# booz_imu_yz.net
KiCad netlist of a schematic drawn in EAGLE
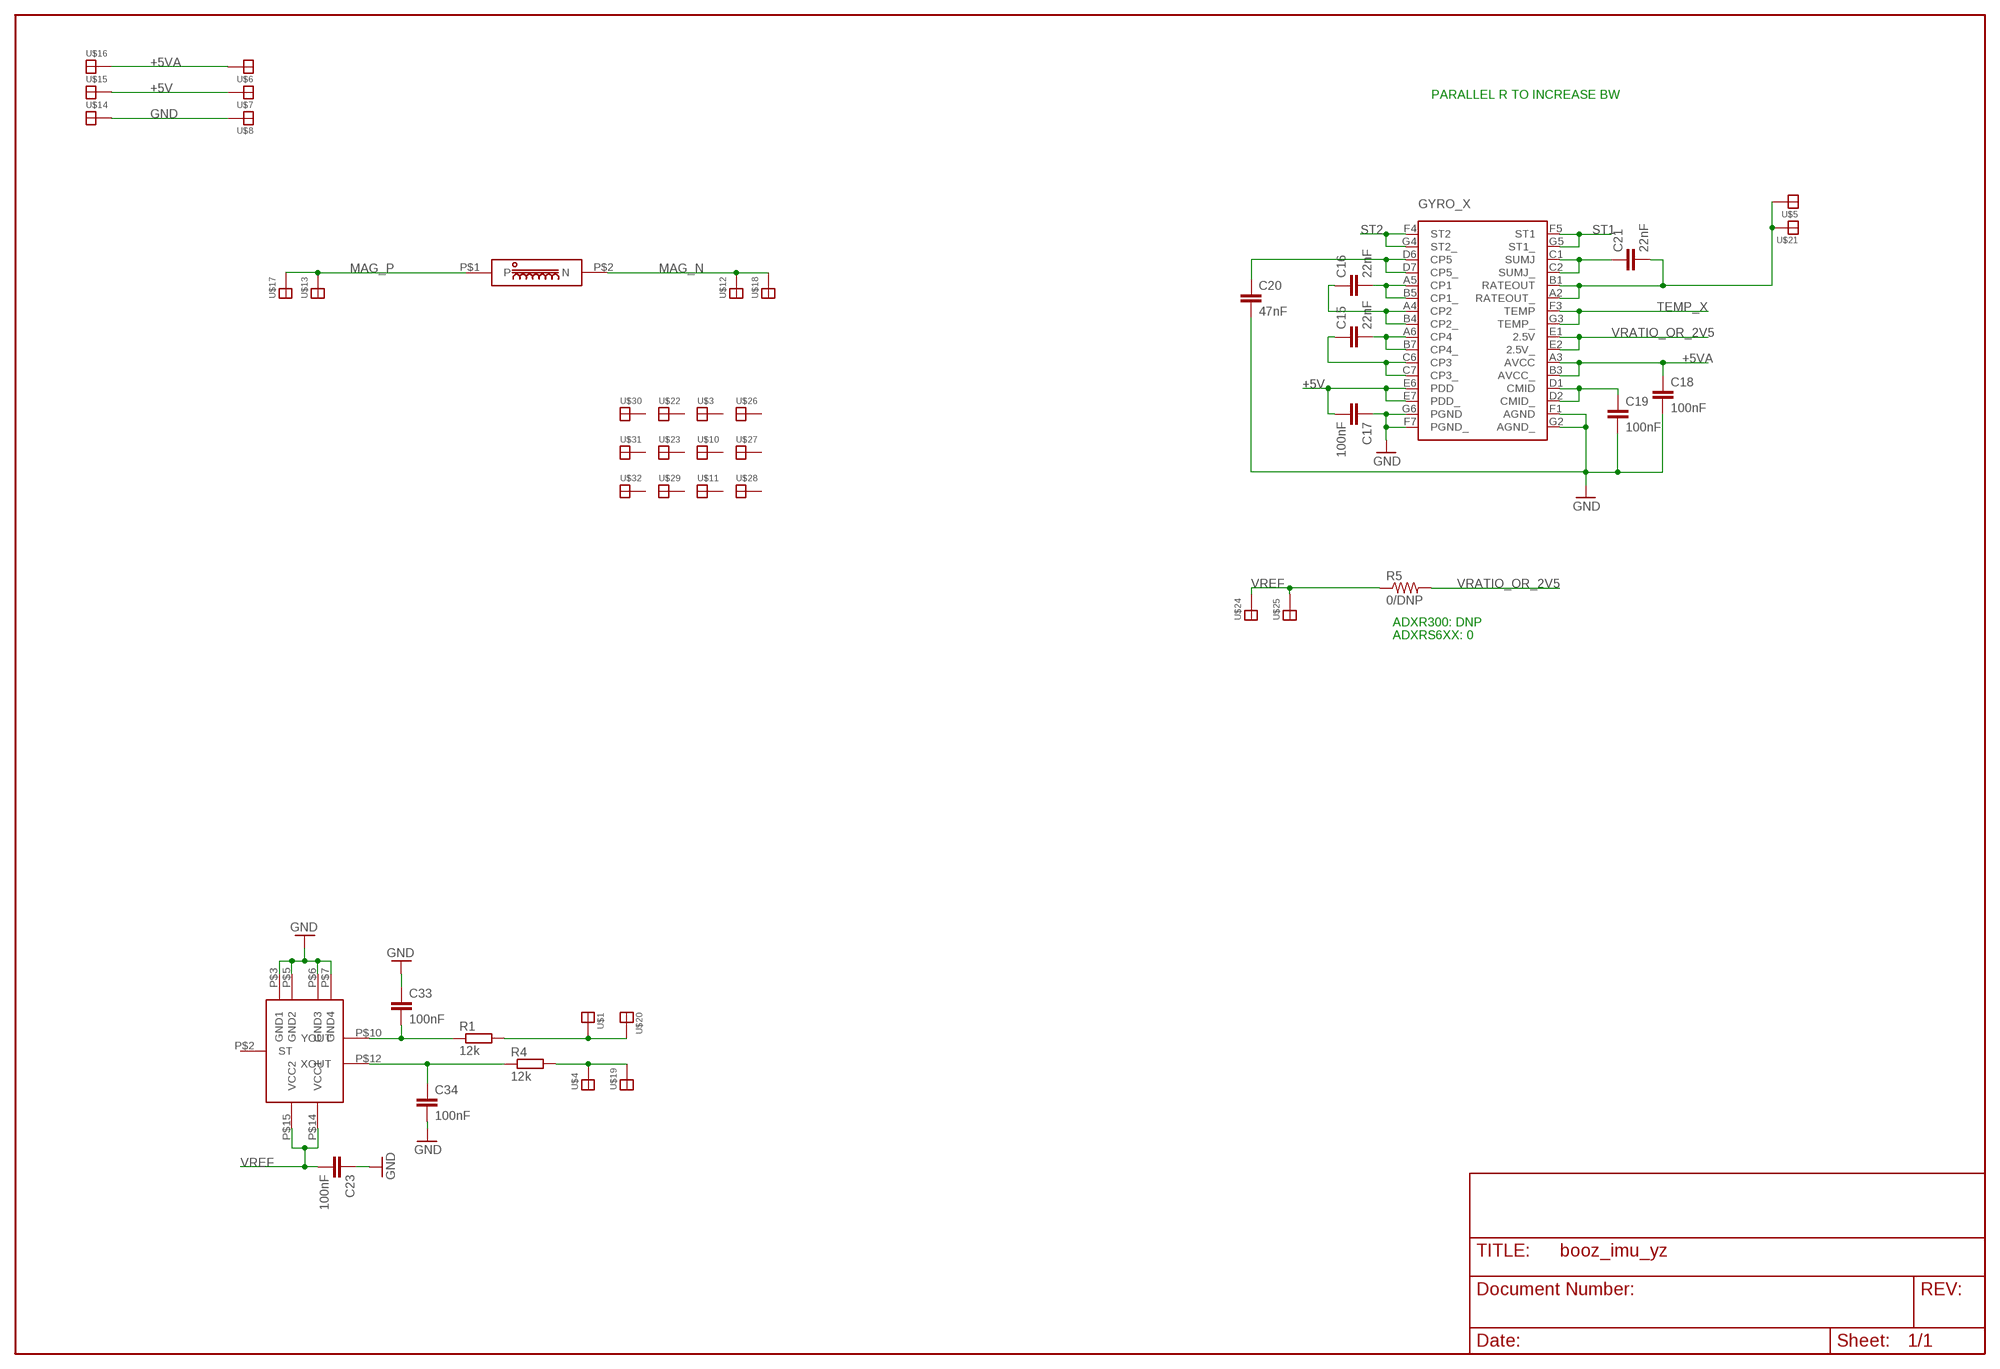
[diagram p0: schematic, sheet 1]

(export (version "E")
  (design (tool "Eeschema 10.0.6"))
  (components
    (comp (ref "C15")
      (value "22nF")
      (footprint "eagle-import:C0603K")
      (libsource (lib "eagle-import") (part "C-EUC0603K"))
    )
    (comp (ref "C16")
      (value "22nF")
      (footprint "eagle-import:C0603K")
      (libsource (lib "eagle-import") (part "C-EUC0603K"))
    )
    (comp (ref "C17")
      (value "100nF")
      (footprint "eagle-import:C0603K")
      (libsource (lib "eagle-import") (part "C-EUC0603K"))
    )
    (comp (ref "C18")
      (value "100nF")
      (footprint "eagle-import:C0603K")
      (libsource (lib "eagle-import") (part "C-EUC0603K"))
    )
    (comp (ref "C19")
      (value "100nF")
      (footprint "eagle-import:C0603K")
      (libsource (lib "eagle-import") (part "C-EUC0603K"))
    )
    (comp (ref "C20")
      (value "47nF")
      (footprint "eagle-import:C0603K")
      (libsource (lib "eagle-import") (part "C-EUC0603K"))
    )
    (comp (ref "C21")
      (value "22nF")
      (footprint "eagle-import:C0603K")
      (libsource (lib "eagle-import") (part "C-EUC0603K"))
    )
    (comp (ref "C23")
      (value "100nF")
      (footprint "eagle-import:C0603K")
      (libsource (lib "eagle-import") (part "C-EUC0603K"))
    )
    (comp (ref "C33")
      (value "100nF")
      (footprint "eagle-import:C0603K")
      (libsource (lib "eagle-import") (part "C-EUC0603K"))
    )
    (comp (ref "C34")
      (value "100nF")
      (footprint "eagle-import:C0603K")
      (libsource (lib "eagle-import") (part "C-EUC0603K"))
    )
    (comp (ref "GYRO_X")
      (value "ADXR")
      (footprint "eagle-import:BC-32")
      (libsource (lib "eagle-import") (part "ADXR"))
    )
    (comp (ref "R1")
      (value "12k")
      (footprint "eagle-import:R0603")
      (libsource (lib "eagle-import") (part "R-EU_R0603"))
    )
    (comp (ref "R4")
      (value "12k")
      (footprint "eagle-import:R0603")
      (libsource (lib "eagle-import") (part "R-EU_R0603"))
    )
    (comp (ref "R5")
      (value "0/DNP")
      (footprint "eagle-import:R0603")
      (libsource (lib "eagle-import") (part "R-US_R0603"))
    )
    (comp (ref "U$1")
      (value "SOLDER_PAD")
      (footprint "eagle-import:SOLDER_PAD")
      (libsource (lib "eagle-import") (part "SOLDER_PAD"))
    )
    (comp (ref "U$2")
      (value "ADXL320")
      (footprint "eagle-import:LSCFP")
      (libsource (lib "eagle-import") (part "ADXL320"))
    )
    (comp (ref "U$3")
      (value "SOLDER_PAD")
      (footprint "eagle-import:SOLDER_PAD")
      (libsource (lib "eagle-import") (part "SOLDER_PAD"))
    )
    (comp (ref "U$4")
      (value "SOLDER_PAD")
      (footprint "eagle-import:SOLDER_PAD")
      (libsource (lib "eagle-import") (part "SOLDER_PAD"))
    )
    (comp (ref "U$5")
      (value "SOLDER_PAD")
      (footprint "eagle-import:SOLDER_PAD")
      (libsource (lib "eagle-import") (part "SOLDER_PAD"))
    )
    (comp (ref "U$6")
      (value "SOLDER_PAD")
      (footprint "eagle-import:SOLDER_PAD")
      (libsource (lib "eagle-import") (part "SOLDER_PAD"))
    )
    (comp (ref "U$7")
      (value "SOLDER_PAD")
      (footprint "eagle-import:SOLDER_PAD")
      (libsource (lib "eagle-import") (part "SOLDER_PAD"))
    )
    (comp (ref "U$8")
      (value "SOLDER_PAD")
      (footprint "eagle-import:SOLDER_PAD")
      (libsource (lib "eagle-import") (part "SOLDER_PAD"))
    )
    (comp (ref "U$9")
      (value "SEN_XY")
      (footprint "eagle-import:SEN_XY")
      (libsource (lib "eagle-import") (part "SEN_XY"))
    )
    (comp (ref "U$10")
      (value "SOLDER_PAD")
      (footprint "eagle-import:SOLDER_PAD")
      (libsource (lib "eagle-import") (part "SOLDER_PAD"))
    )
    (comp (ref "U$11")
      (value "SOLDER_PAD")
      (footprint "eagle-import:SOLDER_PAD")
      (libsource (lib "eagle-import") (part "SOLDER_PAD"))
    )
    (comp (ref "U$12")
      (value "SOLDER_PAD")
      (footprint "eagle-import:SOLDER_PAD")
      (libsource (lib "eagle-import") (part "SOLDER_PAD"))
    )
    (comp (ref "U$13")
      (value "SOLDER_PAD")
      (footprint "eagle-import:SOLDER_PAD")
      (libsource (lib "eagle-import") (part "SOLDER_PAD"))
    )
    (comp (ref "U$14")
      (value "SOLDER_PAD")
      (footprint "eagle-import:SOLDER_PAD")
      (libsource (lib "eagle-import") (part "SOLDER_PAD"))
    )
    (comp (ref "U$15")
      (value "SOLDER_PAD")
      (footprint "eagle-import:SOLDER_PAD")
      (libsource (lib "eagle-import") (part "SOLDER_PAD"))
    )
    (comp (ref "U$16")
      (value "SOLDER_PAD")
      (footprint "eagle-import:SOLDER_PAD")
      (libsource (lib "eagle-import") (part "SOLDER_PAD"))
    )
    (comp (ref "U$17")
      (value "SOLDER_PAD")
      (footprint "eagle-import:SOLDER_PAD")
      (libsource (lib "eagle-import") (part "SOLDER_PAD"))
    )
    (comp (ref "U$18")
      (value "SOLDER_PAD")
      (footprint "eagle-import:SOLDER_PAD")
      (libsource (lib "eagle-import") (part "SOLDER_PAD"))
    )
    (comp (ref "U$19")
      (value "SOLDER_PAD")
      (footprint "eagle-import:SOLDER_PAD")
      (libsource (lib "eagle-import") (part "SOLDER_PAD"))
    )
    (comp (ref "U$20")
      (value "SOLDER_PAD")
      (footprint "eagle-import:SOLDER_PAD")
      (libsource (lib "eagle-import") (part "SOLDER_PAD"))
    )
    (comp (ref "U$21")
      (value "SOLDER_PAD")
      (footprint "eagle-import:SOLDER_PAD")
      (libsource (lib "eagle-import") (part "SOLDER_PAD"))
    )
    (comp (ref "U$22")
      (value "SOLDER_PAD")
      (footprint "eagle-import:SOLDER_PAD")
      (libsource (lib "eagle-import") (part "SOLDER_PAD"))
    )
    (comp (ref "U$23")
      (value "SOLDER_PAD")
      (footprint "eagle-import:SOLDER_PAD")
      (libsource (lib "eagle-import") (part "SOLDER_PAD"))
    )
    (comp (ref "U$24")
      (value "SOLDER_PAD")
      (footprint "eagle-import:SOLDER_PAD")
      (libsource (lib "eagle-import") (part "SOLDER_PAD"))
    )
    (comp (ref "U$25")
      (value "SOLDER_PAD")
      (footprint "eagle-import:SOLDER_PAD")
      (libsource (lib "eagle-import") (part "SOLDER_PAD"))
    )
    (comp (ref "U$26")
      (value "SOLDER_PAD")
      (footprint "eagle-import:SOLDER_PAD")
      (libsource (lib "eagle-import") (part "SOLDER_PAD"))
    )
    (comp (ref "U$27")
      (value "SOLDER_PAD")
      (footprint "eagle-import:SOLDER_PAD")
      (libsource (lib "eagle-import") (part "SOLDER_PAD"))
    )
    (comp (ref "U$28")
      (value "SOLDER_PAD")
      (footprint "eagle-import:SOLDER_PAD")
      (libsource (lib "eagle-import") (part "SOLDER_PAD"))
    )
    (comp (ref "U$29")
      (value "SOLDER_PAD")
      (footprint "eagle-import:SOLDER_PAD")
      (libsource (lib "eagle-import") (part "SOLDER_PAD"))
    )
    (comp (ref "U$30")
      (value "SOLDER_PAD")
      (footprint "eagle-import:SOLDER_PAD")
      (libsource (lib "eagle-import") (part "SOLDER_PAD"))
    )
    (comp (ref "U$31")
      (value "SOLDER_PAD")
      (footprint "eagle-import:SOLDER_PAD")
      (libsource (lib "eagle-import") (part "SOLDER_PAD"))
    )
    (comp (ref "U$32")
      (value "SOLDER_PAD")
      (footprint "eagle-import:SOLDER_PAD")
      (libsource (lib "eagle-import") (part "SOLDER_PAD"))
    )
  )
  (nets
    (net (code "1") (name "/+5V") (class "Default")
      (node (ref "C17") (pin "2") (pinfunction "2_2") (pintype "passive"))
      (node (ref "GYRO_X") (pin "E6") (pinfunction "PDD_E6") (pintype "bidirectional"))
      (node (ref "GYRO_X") (pin "E7") (pinfunction "PDD__E7") (pintype "bidirectional"))
      (node (ref "U$15") (pin "P$1") (pinfunction "P$1_P$1") (pintype "bidirectional"))
      (node (ref "U$7") (pin "P$1") (pinfunction "P$1_P$1") (pintype "bidirectional"))
    )
    (net (code "2") (name "/+5VA") (class "Default")
      (node (ref "C18") (pin "1") (pinfunction "1_1") (pintype "passive"))
      (node (ref "GYRO_X") (pin "A3") (pinfunction "AVCC_A3") (pintype "bidirectional"))
      (node (ref "GYRO_X") (pin "B3") (pinfunction "AVCC__B3") (pintype "bidirectional"))
      (node (ref "U$16") (pin "P$1") (pinfunction "P$1_P$1") (pintype "bidirectional"))
      (node (ref "U$6") (pin "P$1") (pinfunction "P$1_P$1") (pintype "bidirectional"))
    )
    (net (code "3") (name "/MAG_N") (class "Default")
      (node (ref "U$12") (pin "P$1") (pinfunction "P$1_P$1") (pintype "bidirectional"))
      (node (ref "U$18") (pin "P$1") (pinfunction "P$1_P$1") (pintype "bidirectional"))
      (node (ref "U$9") (pin "P$2") (pinfunction "N_P$2") (pintype "bidirectional"))
    )
    (net (code "4") (name "/MAG_P") (class "Default")
      (node (ref "U$13") (pin "P$1") (pinfunction "P$1_P$1") (pintype "bidirectional"))
      (node (ref "U$17") (pin "P$1") (pinfunction "P$1_P$1") (pintype "bidirectional"))
      (node (ref "U$9") (pin "P$1") (pinfunction "P_P$1") (pintype "bidirectional"))
    )
    (net (code "5") (name "/ST1") (class "Default")
      (node (ref "GYRO_X") (pin "F5") (pinfunction "ST1_F5") (pintype "bidirectional"))
      (node (ref "GYRO_X") (pin "G5") (pinfunction "ST1__G5") (pintype "bidirectional"))
    )
    (net (code "6") (name "/ST2") (class "Default")
      (node (ref "GYRO_X") (pin "F4") (pinfunction "ST2_F4") (pintype "bidirectional"))
      (node (ref "GYRO_X") (pin "G4") (pinfunction "ST2__G4") (pintype "bidirectional"))
    )
    (net (code "7") (name "/TEMP_X") (class "Default")
      (node (ref "GYRO_X") (pin "F3") (pinfunction "TEMP_F3") (pintype "bidirectional"))
      (node (ref "GYRO_X") (pin "G3") (pinfunction "TEMP__G3") (pintype "bidirectional"))
    )
    (net (code "8") (name "/VRATIO_OR_2V5") (class "Default")
      (node (ref "GYRO_X") (pin "E1") (pinfunction "2.5V_E1") (pintype "bidirectional"))
      (node (ref "GYRO_X") (pin "E2") (pinfunction "2.5V__E2") (pintype "bidirectional"))
      (node (ref "R5") (pin "2") (pinfunction "2_2") (pintype "passive"))
    )
    (net (code "9") (name "/VREF") (class "Default")
      (node (ref "C23") (pin "2") (pinfunction "2_2") (pintype "passive"))
      (node (ref "R5") (pin "1") (pinfunction "1_1") (pintype "passive"))
      (node (ref "U$2") (pin "P$14") (pinfunction "VCC1_P$14") (pintype "bidirectional"))
      (node (ref "U$2") (pin "P$15") (pinfunction "VCC2_P$15") (pintype "bidirectional"))
      (node (ref "U$24") (pin "P$1") (pinfunction "P$1_P$1") (pintype "bidirectional"))
      (node (ref "U$25") (pin "P$1") (pinfunction "P$1_P$1") (pintype "bidirectional"))
    )
    (net (code "10") (name "GND") (class "Default")
      (node (ref "C17") (pin "1") (pinfunction "1_1") (pintype "passive"))
      (node (ref "C18") (pin "2") (pinfunction "2_2") (pintype "passive"))
      (node (ref "C19") (pin "2") (pinfunction "2_2") (pintype "passive"))
      (node (ref "C20") (pin "2") (pinfunction "2_2") (pintype "passive"))
      (node (ref "C23") (pin "1") (pinfunction "1_1") (pintype "passive"))
      (node (ref "C33") (pin "1") (pinfunction "1_1") (pintype "passive"))
      (node (ref "C34") (pin "2") (pinfunction "2_2") (pintype "passive"))
      (node (ref "GYRO_X") (pin "F1") (pinfunction "AGND_F1") (pintype "bidirectional"))
      (node (ref "GYRO_X") (pin "F7") (pinfunction "PGND__F7") (pintype "bidirectional"))
      (node (ref "GYRO_X") (pin "G2") (pinfunction "AGND__G2") (pintype "bidirectional"))
      (node (ref "GYRO_X") (pin "G6") (pinfunction "PGND_G6") (pintype "bidirectional"))
      (node (ref "U$14") (pin "P$1") (pinfunction "P$1_P$1") (pintype "bidirectional"))
      (node (ref "U$2") (pin "P$3") (pinfunction "GND1_P$3") (pintype "bidirectional"))
      (node (ref "U$2") (pin "P$5") (pinfunction "GND2_P$5") (pintype "bidirectional"))
      (node (ref "U$2") (pin "P$6") (pinfunction "GND3_P$6") (pintype "bidirectional"))
      (node (ref "U$2") (pin "P$7") (pinfunction "GND4_P$7") (pintype "bidirectional"))
      (node (ref "U$8") (pin "P$1") (pinfunction "P$1_P$1") (pintype "bidirectional"))
    )
    (net (code "11") (name "Net-(GYRO_X-CMID)") (class "Default")
      (node (ref "C19") (pin "1") (pinfunction "1_1") (pintype "passive"))
      (node (ref "GYRO_X") (pin "D1") (pinfunction "CMID_D1") (pintype "bidirectional"))
      (node (ref "GYRO_X") (pin "D2") (pinfunction "CMID__D2") (pintype "bidirectional"))
    )
    (net (code "12") (name "Net-(GYRO_X-CP1)") (class "Default")
      (node (ref "C16") (pin "2") (pinfunction "2_2") (pintype "passive"))
      (node (ref "GYRO_X") (pin "A5") (pinfunction "CP1_A5") (pintype "bidirectional"))
      (node (ref "GYRO_X") (pin "B5") (pinfunction "CP1__B5") (pintype "bidirectional"))
    )
    (net (code "13") (name "Net-(GYRO_X-CP2)") (class "Default")
      (node (ref "C16") (pin "1") (pinfunction "1_1") (pintype "passive"))
      (node (ref "GYRO_X") (pin "A4") (pinfunction "CP2_A4") (pintype "bidirectional"))
      (node (ref "GYRO_X") (pin "B4") (pinfunction "CP2__B4") (pintype "bidirectional"))
    )
    (net (code "14") (name "Net-(GYRO_X-CP3)") (class "Default")
      (node (ref "C15") (pin "1") (pinfunction "1_1") (pintype "passive"))
      (node (ref "GYRO_X") (pin "C6") (pinfunction "CP3_C6") (pintype "bidirectional"))
      (node (ref "GYRO_X") (pin "C7") (pinfunction "CP3__C7") (pintype "bidirectional"))
    )
    (net (code "15") (name "Net-(GYRO_X-CP4)") (class "Default")
      (node (ref "C15") (pin "2") (pinfunction "2_2") (pintype "passive"))
      (node (ref "GYRO_X") (pin "A6") (pinfunction "CP4_A6") (pintype "bidirectional"))
      (node (ref "GYRO_X") (pin "B7") (pinfunction "CP4__B7") (pintype "bidirectional"))
    )
    (net (code "16") (name "Net-(GYRO_X-CP5)") (class "Default")
      (node (ref "C20") (pin "1") (pinfunction "1_1") (pintype "passive"))
      (node (ref "GYRO_X") (pin "D6") (pinfunction "CP5_D6") (pintype "bidirectional"))
      (node (ref "GYRO_X") (pin "D7") (pinfunction "CP5__D7") (pintype "bidirectional"))
    )
    (net (code "17") (name "Net-(GYRO_X-RATEOUT)") (class "Default")
      (node (ref "C21") (pin "2") (pinfunction "2_2") (pintype "passive"))
      (node (ref "GYRO_X") (pin "A2") (pinfunction "RATEOUT__A2") (pintype "bidirectional"))
      (node (ref "GYRO_X") (pin "B1") (pinfunction "RATEOUT_B1") (pintype "bidirectional"))
      (node (ref "U$21") (pin "P$1") (pinfunction "P$1_P$1") (pintype "bidirectional"))
      (node (ref "U$5") (pin "P$1") (pinfunction "P$1_P$1") (pintype "bidirectional"))
    )
    (net (code "18") (name "Net-(GYRO_X-SUMJ)") (class "Default")
      (node (ref "C21") (pin "1") (pinfunction "1_1") (pintype "passive"))
      (node (ref "GYRO_X") (pin "C1") (pinfunction "SUMJ_C1") (pintype "bidirectional"))
      (node (ref "GYRO_X") (pin "C2") (pinfunction "SUMJ__C2") (pintype "bidirectional"))
    )
    (net (code "19") (name "Net-(R1-Pad2)") (class "Default")
      (node (ref "R1") (pin "2") (pinfunction "2_2") (pintype "passive"))
      (node (ref "U$1") (pin "P$1") (pinfunction "P$1_P$1") (pintype "bidirectional"))
      (node (ref "U$20") (pin "P$1") (pinfunction "P$1_P$1") (pintype "bidirectional"))
    )
    (net (code "20") (name "Net-(R4-Pad2)") (class "Default")
      (node (ref "R4") (pin "2") (pinfunction "2_2") (pintype "passive"))
      (node (ref "U$19") (pin "P$1") (pinfunction "P$1_P$1") (pintype "bidirectional"))
      (node (ref "U$4") (pin "P$1") (pinfunction "P$1_P$1") (pintype "bidirectional"))
    )
    (net (code "21") (name "Net-(U$2-XOUT)") (class "Default")
      (node (ref "C34") (pin "1") (pinfunction "1_1") (pintype "passive"))
      (node (ref "R4") (pin "1") (pinfunction "1_1") (pintype "passive"))
      (node (ref "U$2") (pin "P$12") (pinfunction "XOUT_P$12") (pintype "bidirectional"))
    )
    (net (code "22") (name "Net-(U$2-YOUT)") (class "Default")
      (node (ref "C33") (pin "2") (pinfunction "2_2") (pintype "passive"))
      (node (ref "R1") (pin "1") (pinfunction "1_1") (pintype "passive"))
      (node (ref "U$2") (pin "P$10") (pinfunction "YOUT_P$10") (pintype "bidirectional"))
    )
    (net (code "23") (name "unconnected-(U$2-ST-PadP$2)") (class "Default")
      (node (ref "U$2") (pin "P$2") (pinfunction "ST_P$2") (pintype "bidirectional"))
    )
    (net (code "24") (name "unconnected-(U$3-PadP$1)") (class "Default")
      (node (ref "U$3") (pin "P$1") (pinfunction "P$1_P$1") (pintype "bidirectional"))
    )
    (net (code "25") (name "unconnected-(U$10-PadP$1)") (class "Default")
      (node (ref "U$10") (pin "P$1") (pinfunction "P$1_P$1") (pintype "bidirectional"))
    )
    (net (code "26") (name "unconnected-(U$11-PadP$1)") (class "Default")
      (node (ref "U$11") (pin "P$1") (pinfunction "P$1_P$1") (pintype "bidirectional"))
    )
    (net (code "27") (name "unconnected-(U$22-PadP$1)") (class "Default")
      (node (ref "U$22") (pin "P$1") (pinfunction "P$1_P$1") (pintype "bidirectional"))
    )
    (net (code "28") (name "unconnected-(U$23-PadP$1)") (class "Default")
      (node (ref "U$23") (pin "P$1") (pinfunction "P$1_P$1") (pintype "bidirectional"))
    )
    (net (code "29") (name "unconnected-(U$26-PadP$1)") (class "Default")
      (node (ref "U$26") (pin "P$1") (pinfunction "P$1_P$1") (pintype "bidirectional"))
    )
    (net (code "30") (name "unconnected-(U$27-PadP$1)") (class "Default")
      (node (ref "U$27") (pin "P$1") (pinfunction "P$1_P$1") (pintype "bidirectional"))
    )
    (net (code "31") (name "unconnected-(U$28-PadP$1)") (class "Default")
      (node (ref "U$28") (pin "P$1") (pinfunction "P$1_P$1") (pintype "bidirectional"))
    )
    (net (code "32") (name "unconnected-(U$29-PadP$1)") (class "Default")
      (node (ref "U$29") (pin "P$1") (pinfunction "P$1_P$1") (pintype "bidirectional"))
    )
    (net (code "33") (name "unconnected-(U$30-PadP$1)") (class "Default")
      (node (ref "U$30") (pin "P$1") (pinfunction "P$1_P$1") (pintype "bidirectional"))
    )
    (net (code "34") (name "unconnected-(U$31-PadP$1)") (class "Default")
      (node (ref "U$31") (pin "P$1") (pinfunction "P$1_P$1") (pintype "bidirectional"))
    )
    (net (code "35") (name "unconnected-(U$32-PadP$1)") (class "Default")
      (node (ref "U$32") (pin "P$1") (pinfunction "P$1_P$1") (pintype "bidirectional"))
    )
  )
)
